# Schematic.net
KiCad netlist of a schematic drawn in Altium Designer
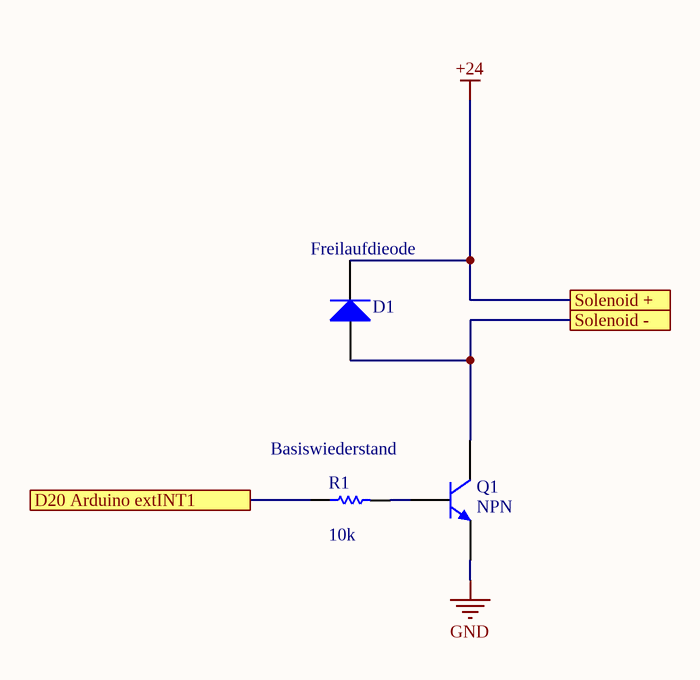
[diagram p0: Schematic.SchDoc]

(export (version "E")
  (design (tool "Eeschema 10.0.6"))
  (components
    (comp (ref "D1")
      (value "Freilaufdieode")
      (footprint "SMC")
      (description "Default Diode")
      (fields (field (name "PUBLISHER") "Altium Limited"))
      (libsource (lib "Miscellaneous Devices") (part "Diode"))
    )
    (comp (ref "Q1")
      (value "NPN")
      (footprint "TO-226-AA")
      (description "NPN Bipolar Transistor")
      (fields (field (name "PUBLISHER") "Altium Limited"))
      (libsource (lib "Miscellaneous Devices") (part "NPN"))
    )
    (comp (ref "R1")
      (value "Basiswiederstand")
      (footprint "AXIAL-0.3")
      (description "Resistor")
      (fields (field (name "ALTIUM_VALUE") "10k") (field (name "PUBLISHER") "Altium Limited"))
      (libsource (lib "Miscellaneous Devices") (part "Res1"))
    )
  )
  (nets
    (net (code "1") (name "+24") (class "Default")
      (node (ref "D1") (pin "2") (pinfunction "K_2") (pintype "passive"))
    )
    (net (code "2") (name "/D20 Arduino extINT1") (class "Default")
      (node (ref "R1") (pin "1") (pinfunction "1_1") (pintype "passive"))
    )
    (net (code "3") (name "/Solenoid -") (class "Default")
      (node (ref "D1") (pin "1") (pinfunction "A_1") (pintype "passive"))
      (node (ref "Q1") (pin "1") (pinfunction "C_1") (pintype "passive"))
    )
    (net (code "4") (name "GND") (class "Default")
      (node (ref "Q1") (pin "3") (pinfunction "E_3") (pintype "passive"))
    )
    (net (code "5") (name "Net-(Q1-B)") (class "Default")
      (node (ref "Q1") (pin "2") (pinfunction "B_2") (pintype "passive"))
      (node (ref "R1") (pin "2") (pinfunction "2_2") (pintype "passive"))
    )
  )
)
